# button_module.net
KiCad netlist of a schematic drawn in EAGLE
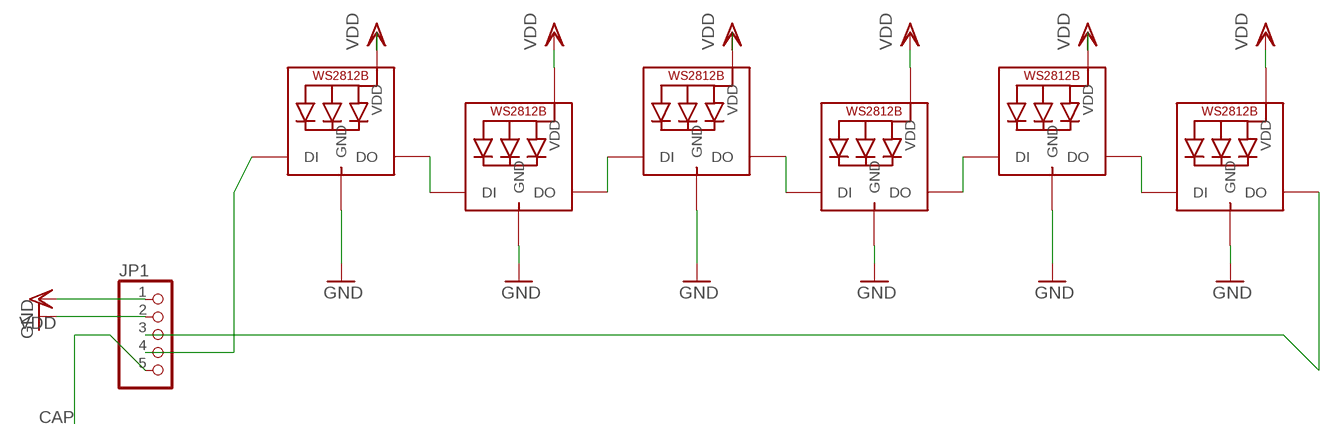
[diagram p0: schematic, sheet 1]

(export (version "E")
  (design (tool "Eeschema 10.0.6"))
  (components
    (comp (ref "JP1")
      (value "PINHD-1X5")
      (footprint "eagle-import:1X05")
      (libsource (lib "eagle-import") (part "PINHD-1X5"))
    )
    (comp (ref "LED1")
      (value "WS2812B5050")
      (footprint "eagle-import:WS2812B")
      (libsource (lib "eagle-import") (part "WS2812B5050"))
    )
    (comp (ref "LED2")
      (value "WS2812B5050")
      (footprint "eagle-import:WS2812B")
      (libsource (lib "eagle-import") (part "WS2812B5050"))
    )
    (comp (ref "LED3")
      (value "WS2812B5050")
      (footprint "eagle-import:WS2812B")
      (libsource (lib "eagle-import") (part "WS2812B5050"))
    )
    (comp (ref "LED4")
      (value "WS2812B5050")
      (footprint "eagle-import:WS2812B")
      (libsource (lib "eagle-import") (part "WS2812B5050"))
    )
    (comp (ref "LED5")
      (value "WS2812B5050")
      (footprint "eagle-import:WS2812B")
      (libsource (lib "eagle-import") (part "WS2812B5050"))
    )
    (comp (ref "LED6")
      (value "WS2812B5050")
      (footprint "eagle-import:WS2812B")
      (libsource (lib "eagle-import") (part "WS2812B5050"))
    )
  )
  (nets
    (net (code "1") (name "/CAP") (class "Default")
      (node (ref "JP1") (pin "5") (pinfunction "5_5") (pintype "passive"))
    )
    (net (code "2") (name "GND") (class "Default")
      (node (ref "JP1") (pin "2") (pinfunction "2_2") (pintype "passive"))
      (node (ref "LED1") (pin "3-GND") (pinfunction "GND_3-GND") (pintype "power_in"))
      (node (ref "LED2") (pin "3-GND") (pinfunction "GND_3-GND") (pintype "power_in"))
      (node (ref "LED3") (pin "3-GND") (pinfunction "GND_3-GND") (pintype "power_in"))
      (node (ref "LED4") (pin "3-GND") (pinfunction "GND_3-GND") (pintype "power_in"))
      (node (ref "LED5") (pin "3-GND") (pinfunction "GND_3-GND") (pintype "power_in"))
      (node (ref "LED6") (pin "3-GND") (pinfunction "GND_3-GND") (pintype "power_in"))
    )
    (net (code "3") (name "Net-(LED1-DI)") (class "Default")
      (node (ref "JP1") (pin "4") (pinfunction "4_4") (pintype "passive"))
      (node (ref "LED1") (pin "4-DIN") (pinfunction "DI_4-DIN") (pintype "input"))
    )
    (net (code "4") (name "Net-(LED1-DO)") (class "Default")
      (node (ref "LED1") (pin "2-DOUT") (pinfunction "DO_2-DOUT") (pintype "output"))
      (node (ref "LED2") (pin "4-DIN") (pinfunction "DI_4-DIN") (pintype "input"))
    )
    (net (code "5") (name "Net-(LED2-DO)") (class "Default")
      (node (ref "LED2") (pin "2-DOUT") (pinfunction "DO_2-DOUT") (pintype "output"))
      (node (ref "LED3") (pin "4-DIN") (pinfunction "DI_4-DIN") (pintype "input"))
    )
    (net (code "6") (name "Net-(LED3-DO)") (class "Default")
      (node (ref "LED3") (pin "2-DOUT") (pinfunction "DO_2-DOUT") (pintype "output"))
      (node (ref "LED4") (pin "4-DIN") (pinfunction "DI_4-DIN") (pintype "input"))
    )
    (net (code "7") (name "Net-(LED4-DO)") (class "Default")
      (node (ref "LED4") (pin "2-DOUT") (pinfunction "DO_2-DOUT") (pintype "output"))
      (node (ref "LED5") (pin "4-DIN") (pinfunction "DI_4-DIN") (pintype "input"))
    )
    (net (code "8") (name "Net-(LED5-DO)") (class "Default")
      (node (ref "LED5") (pin "2-DOUT") (pinfunction "DO_2-DOUT") (pintype "output"))
      (node (ref "LED6") (pin "4-DIN") (pinfunction "DI_4-DIN") (pintype "input"))
    )
    (net (code "9") (name "Net-(LED6-DO)") (class "Default")
      (node (ref "JP1") (pin "3") (pinfunction "3_3") (pintype "passive"))
      (node (ref "LED6") (pin "2-DOUT") (pinfunction "DO_2-DOUT") (pintype "output"))
    )
    (net (code "10") (name "VDD") (class "Default")
      (node (ref "JP1") (pin "1") (pinfunction "1_1") (pintype "passive"))
      (node (ref "LED1") (pin "1-VDD") (pinfunction "VDD_1-VDD") (pintype "power_in"))
      (node (ref "LED2") (pin "1-VDD") (pinfunction "VDD_1-VDD") (pintype "power_in"))
      (node (ref "LED3") (pin "1-VDD") (pinfunction "VDD_1-VDD") (pintype "power_in"))
      (node (ref "LED4") (pin "1-VDD") (pinfunction "VDD_1-VDD") (pintype "power_in"))
      (node (ref "LED5") (pin "1-VDD") (pinfunction "VDD_1-VDD") (pintype "power_in"))
      (node (ref "LED6") (pin "1-VDD") (pinfunction "VDD_1-VDD") (pintype "power_in"))
    )
  )
)
